# FM_VCO_Transmitter.net
KiCad netlist of a schematic drawn in EAGLE
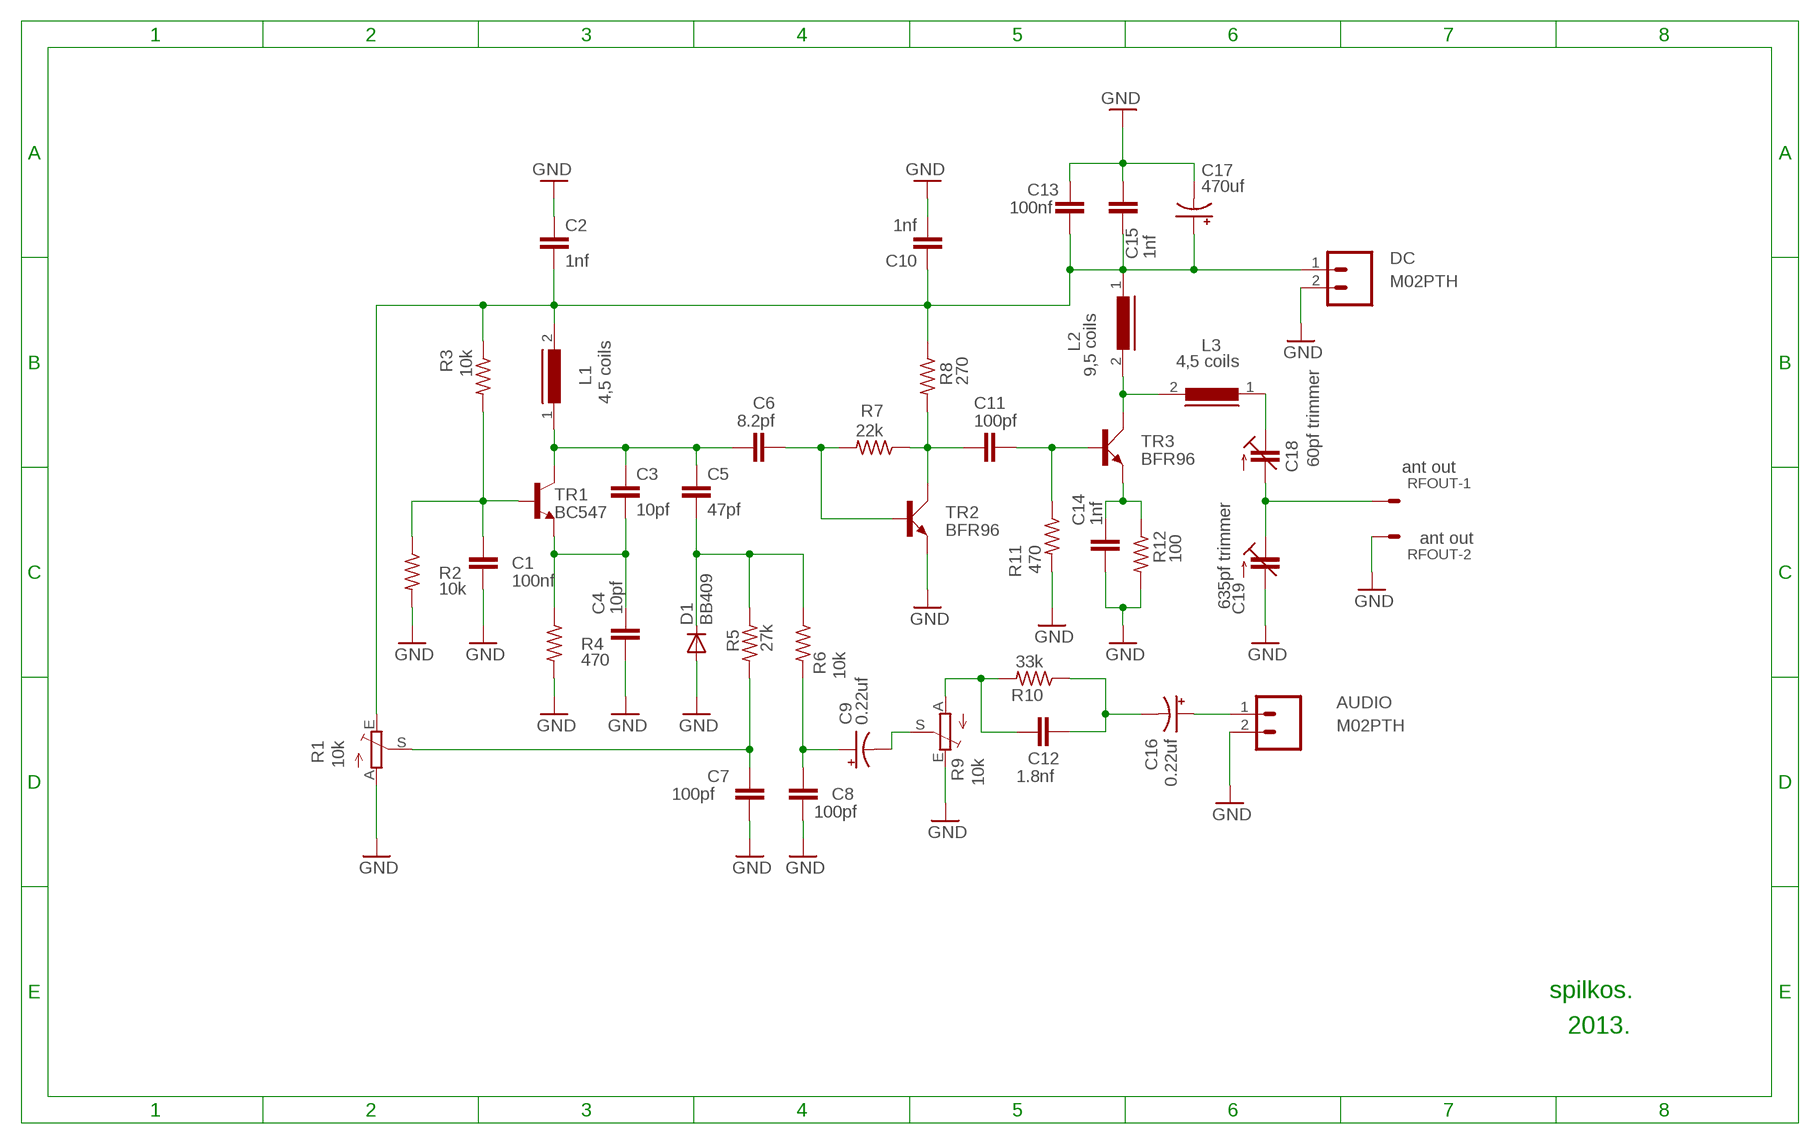
[diagram p0: schematic, sheet 1]

(export (version "E")
  (design (tool "Eeschema 10.0.6"))
  (components
    (comp (ref "AUDIO")
      (value "M02PTH")
      (footprint "eagle-import:1X02")
      (libsource (lib "eagle-import") (part "M02PTH"))
    )
    (comp (ref "C1")
      (value "100nf")
      (footprint "eagle-import:C025-024X044")
      (libsource (lib "eagle-import") (part "C-EU025-024X044"))
    )
    (comp (ref "C2")
      (value "1nf")
      (footprint "eagle-import:C025-024X044")
      (libsource (lib "eagle-import") (part "C-EU025-024X044"))
    )
    (comp (ref "C3")
      (value "10pf")
      (footprint "eagle-import:C025-024X044")
      (libsource (lib "eagle-import") (part "C-EU025-024X044"))
    )
    (comp (ref "C4")
      (value "10pf")
      (footprint "eagle-import:C025-024X044")
      (libsource (lib "eagle-import") (part "C-EU025-024X044"))
    )
    (comp (ref "C5")
      (value "47pf")
      (footprint "eagle-import:C025-024X044")
      (libsource (lib "eagle-import") (part "C-EU025-024X044"))
    )
    (comp (ref "C6")
      (value "8.2pf")
      (footprint "eagle-import:C025-024X044")
      (libsource (lib "eagle-import") (part "C-EU025-024X044"))
    )
    (comp (ref "C7")
      (value "100pf")
      (footprint "eagle-import:C025-024X044")
      (libsource (lib "eagle-import") (part "C-EU025-024X044"))
    )
    (comp (ref "C8")
      (value "100pf")
      (footprint "eagle-import:C025-024X044")
      (libsource (lib "eagle-import") (part "C-EU025-024X044"))
    )
    (comp (ref "C9")
      (value "0.22uf")
      (footprint "eagle-import:E2,5-6E")
      (libsource (lib "eagle-import") (part "CPOL-USE2,5-6E"))
    )
    (comp (ref "C10")
      (value "1nf")
      (footprint "eagle-import:C025-024X044")
      (libsource (lib "eagle-import") (part "C-EU025-024X044"))
    )
    (comp (ref "C11")
      (value "100pf")
      (footprint "eagle-import:C025-024X044")
      (libsource (lib "eagle-import") (part "C-EU025-024X044"))
    )
    (comp (ref "C12")
      (value "1.8nf")
      (footprint "eagle-import:C025-024X044")
      (libsource (lib "eagle-import") (part "C-EU025-024X044"))
    )
    (comp (ref "C13")
      (value "100nf")
      (footprint "eagle-import:C025-024X044")
      (libsource (lib "eagle-import") (part "C-EU025-024X044"))
    )
    (comp (ref "C14")
      (value "1nf")
      (footprint "eagle-import:C025-024X044")
      (libsource (lib "eagle-import") (part "C-EU025-024X044"))
    )
    (comp (ref "C15")
      (value "1nf")
      (footprint "eagle-import:C025-024X044")
      (libsource (lib "eagle-import") (part "C-EU025-024X044"))
    )
    (comp (ref "C16")
      (value "0.22uf")
      (footprint "eagle-import:E2,5-6E")
      (libsource (lib "eagle-import") (part "CPOL-USE2,5-6E"))
    )
    (comp (ref "C17")
      (value "470uf")
      (footprint "eagle-import:E2,5-6E")
      (libsource (lib "eagle-import") (part "CPOL-USE2,5-6E"))
    )
    (comp (ref "C18")
      (value "60pf trimmer")
      (footprint "eagle-import:CTRIMTZ03")
      (libsource (lib "eagle-import") (part "C-TRIMMTZ03"))
    )
    (comp (ref "C19")
      (value "635pf trimmer")
      (footprint "eagle-import:CTRIMTZ03")
      (libsource (lib "eagle-import") (part "C-TRIMMTZ03"))
    )
    (comp (ref "D1")
      (value "BB409")
      (footprint "eagle-import:DO35-10")
      (libsource (lib "eagle-import") (part "BA243A"))
    )
    (comp (ref "DC")
      (value "M02PTH")
      (footprint "eagle-import:1X02")
      (libsource (lib "eagle-import") (part "M02PTH"))
    )
    (comp (ref "L1")
      (value "4,5 coils")
      (footprint "eagle-import:82114R")
      (libsource (lib "eagle-import") (part "82114R"))
    )
    (comp (ref "L2")
      (value "9,5 coils")
      (footprint "eagle-import:82114R")
      (libsource (lib "eagle-import") (part "82114R"))
    )
    (comp (ref "L3")
      (value "4,5 coils")
      (footprint "eagle-import:82114R")
      (libsource (lib "eagle-import") (part "82114R"))
    )
    (comp (ref "R1")
      (value "10k")
      (footprint "eagle-import:B25P")
      (libsource (lib "eagle-import") (part "TRIM_EU-B25P"))
    )
    (comp (ref "R2")
      (value "10k")
      (footprint "eagle-import:0309V")
      (libsource (lib "eagle-import") (part "R-US_0309/V"))
    )
    (comp (ref "R3")
      (value "10k")
      (footprint "eagle-import:0309V")
      (libsource (lib "eagle-import") (part "R-US_0309/V"))
    )
    (comp (ref "R4")
      (value "470")
      (footprint "eagle-import:0309V")
      (libsource (lib "eagle-import") (part "R-US_0309/V"))
    )
    (comp (ref "R5")
      (value "27k")
      (footprint "eagle-import:0309V")
      (libsource (lib "eagle-import") (part "R-US_0309/V"))
    )
    (comp (ref "R6")
      (value "10k")
      (footprint "eagle-import:0309V")
      (libsource (lib "eagle-import") (part "R-US_0309/V"))
    )
    (comp (ref "R7")
      (value "22k")
      (footprint "eagle-import:0309V")
      (libsource (lib "eagle-import") (part "R-US_0309/V"))
    )
    (comp (ref "R8")
      (value "270")
      (footprint "eagle-import:0309V")
      (libsource (lib "eagle-import") (part "R-US_0309/V"))
    )
    (comp (ref "R9")
      (value "10k")
      (footprint "eagle-import:B25P")
      (libsource (lib "eagle-import") (part "TRIM_EU-B25P"))
    )
    (comp (ref "R10")
      (value "33k")
      (footprint "eagle-import:0309V")
      (libsource (lib "eagle-import") (part "R-US_0309/V"))
    )
    (comp (ref "R11")
      (value "470")
      (footprint "eagle-import:0309V")
      (libsource (lib "eagle-import") (part "R-US_0309/V"))
    )
    (comp (ref "R12")
      (value "100")
      (footprint "eagle-import:0309V")
      (libsource (lib "eagle-import") (part "R-US_0309/V"))
    )
    (comp (ref "RFOUT")
      (value "ant out")
      (footprint "eagle-import:332-02")
      (libsource (lib "eagle-import") (part "332-02"))
    )
    (comp (ref "TR1")
      (value "BC547")
      (footprint "eagle-import:TO92")
      (libsource (lib "eagle-import") (part "BC547"))
    )
    (comp (ref "TR2")
      (value "BFR96")
      (footprint "eagle-import:SOT37")
      (libsource (lib "eagle-import") (part "BFR96"))
    )
    (comp (ref "TR3")
      (value "BFR96")
      (footprint "eagle-import:SOT37")
      (libsource (lib "eagle-import") (part "BFR96"))
    )
  )
  (nets
    (net (code "1") (name "GND") (class "Default")
      (node (ref "AUDIO") (pin "2") (pinfunction "2_2") (pintype "passive"))
      (node (ref "C1") (pin "2") (pinfunction "2_2") (pintype "passive"))
      (node (ref "C10") (pin "2") (pinfunction "2_2") (pintype "passive"))
      (node (ref "C13") (pin "1") (pinfunction "1_1") (pintype "passive"))
      (node (ref "C14") (pin "2") (pinfunction "2_2") (pintype "passive"))
      (node (ref "C15") (pin "1") (pinfunction "1_1") (pintype "passive"))
      (node (ref "C17") (pin "-") (pinfunction "-_-") (pintype "passive"))
      (node (ref "C19") (pin "2") (pinfunction "A_2") (pintype "passive"))
      (node (ref "C2") (pin "1") (pinfunction "1_1") (pintype "passive"))
      (node (ref "C4") (pin "2") (pinfunction "2_2") (pintype "passive"))
      (node (ref "C7") (pin "2") (pinfunction "2_2") (pintype "passive"))
      (node (ref "C8") (pin "2") (pinfunction "2_2") (pintype "passive"))
      (node (ref "D1") (pin "A") (pinfunction "A_A") (pintype "passive"))
      (node (ref "DC") (pin "2") (pinfunction "2_2") (pintype "passive"))
      (node (ref "R1") (pin "A") (pinfunction "A_A") (pintype "passive"))
      (node (ref "R11") (pin "2") (pinfunction "2_2") (pintype "passive"))
      (node (ref "R12") (pin "2") (pinfunction "2_2") (pintype "passive"))
      (node (ref "R2") (pin "2") (pinfunction "2_2") (pintype "passive"))
      (node (ref "R4") (pin "2") (pinfunction "2_2") (pintype "passive"))
      (node (ref "R9") (pin "E") (pinfunction "E_E") (pintype "passive"))
      (node (ref "RFOUT") (pin "2") (pinfunction "S_2") (pintype "passive"))
      (node (ref "TR2") (pin "2") (pinfunction "E_2") (pintype "passive"))
    )
    (net (code "2") (name "Net-(AUDIO-Pad1)") (class "Default")
      (node (ref "AUDIO") (pin "1") (pinfunction "1_1") (pintype "passive"))
      (node (ref "C16") (pin "+") (pinfunction "+_+") (pintype "passive"))
    )
    (net (code "3") (name "Net-(C5-Pad2)") (class "Default")
      (node (ref "C5") (pin "2") (pinfunction "2_2") (pintype "passive"))
      (node (ref "D1") (pin "C") (pinfunction "C_C") (pintype "passive"))
      (node (ref "R5") (pin "1") (pinfunction "1_1") (pintype "passive"))
      (node (ref "R6") (pin "1") (pinfunction "1_1") (pintype "passive"))
    )
    (net (code "4") (name "Net-(C7-Pad1)") (class "Default")
      (node (ref "C7") (pin "1") (pinfunction "1_1") (pintype "passive"))
      (node (ref "R1") (pin "S") (pinfunction "S_S") (pintype "passive"))
      (node (ref "R5") (pin "2") (pinfunction "2_2") (pintype "passive"))
    )
    (net (code "5") (name "Net-(C8-Pad1)") (class "Default")
      (node (ref "C8") (pin "1") (pinfunction "1_1") (pintype "passive"))
      (node (ref "C9") (pin "+") (pinfunction "+_+") (pintype "passive"))
      (node (ref "R6") (pin "2") (pinfunction "2_2") (pintype "passive"))
    )
    (net (code "6") (name "Net-(C9-Pad-)") (class "Default")
      (node (ref "C9") (pin "-") (pinfunction "-_-") (pintype "passive"))
      (node (ref "R9") (pin "S") (pinfunction "S_S") (pintype "passive"))
    )
    (net (code "7") (name "Net-(C10-Pad1)") (class "Default")
      (node (ref "C10") (pin "1") (pinfunction "1_1") (pintype "passive"))
      (node (ref "C13") (pin "2") (pinfunction "2_2") (pintype "passive"))
      (node (ref "C15") (pin "2") (pinfunction "2_2") (pintype "passive"))
      (node (ref "C17") (pin "+") (pinfunction "+_+") (pintype "passive"))
      (node (ref "C2") (pin "2") (pinfunction "2_2") (pintype "passive"))
      (node (ref "DC") (pin "1") (pinfunction "1_1") (pintype "passive"))
      (node (ref "L1") (pin "2") (pinfunction "2_2") (pintype "passive"))
      (node (ref "L2") (pin "1") (pinfunction "1_1") (pintype "passive"))
      (node (ref "R1") (pin "E") (pinfunction "E_E") (pintype "passive"))
      (node (ref "R3") (pin "1") (pinfunction "1_1") (pintype "passive"))
      (node (ref "R8") (pin "1") (pinfunction "1_1") (pintype "passive"))
    )
    (net (code "8") (name "Net-(C12-Pad1)") (class "Default")
      (node (ref "C12") (pin "1") (pinfunction "1_1") (pintype "passive"))
      (node (ref "R10") (pin "2") (pinfunction "2_2") (pintype "passive"))
      (node (ref "R9") (pin "A") (pinfunction "A_A") (pintype "passive"))
    )
    (net (code "9") (name "Net-(C12-Pad2)") (class "Default")
      (node (ref "C12") (pin "2") (pinfunction "2_2") (pintype "passive"))
      (node (ref "C16") (pin "-") (pinfunction "-_-") (pintype "passive"))
      (node (ref "R10") (pin "1") (pinfunction "1_1") (pintype "passive"))
    )
    (net (code "10") (name "Net-(C18-A)") (class "Default")
      (node (ref "C18") (pin "2") (pinfunction "A_2") (pintype "passive"))
      (node (ref "C19") (pin "1") (pinfunction "E_1") (pintype "passive"))
      (node (ref "RFOUT") (pin "1") (pinfunction "S_1") (pintype "passive"))
    )
    (net (code "11") (name "Net-(C18-E)") (class "Default")
      (node (ref "C18") (pin "1") (pinfunction "E_1") (pintype "passive"))
      (node (ref "L3") (pin "1") (pinfunction "1_1") (pintype "passive"))
    )
    (net (code "12") (name "Net-(TR1-B)") (class "Default")
      (node (ref "C1") (pin "1") (pinfunction "1_1") (pintype "passive"))
      (node (ref "R2") (pin "1") (pinfunction "1_1") (pintype "passive"))
      (node (ref "R3") (pin "2") (pinfunction "2_2") (pintype "passive"))
      (node (ref "TR1") (pin "2") (pinfunction "B_2") (pintype "passive"))
    )
    (net (code "13") (name "Net-(TR1-C)") (class "Default")
      (node (ref "C3") (pin "1") (pinfunction "1_1") (pintype "passive"))
      (node (ref "C5") (pin "1") (pinfunction "1_1") (pintype "passive"))
      (node (ref "C6") (pin "1") (pinfunction "1_1") (pintype "passive"))
      (node (ref "L1") (pin "1") (pinfunction "1_1") (pintype "passive"))
      (node (ref "TR1") (pin "3") (pinfunction "C_3") (pintype "passive"))
    )
    (net (code "14") (name "Net-(TR1-E)") (class "Default")
      (node (ref "C3") (pin "2") (pinfunction "2_2") (pintype "passive"))
      (node (ref "C4") (pin "1") (pinfunction "1_1") (pintype "passive"))
      (node (ref "R4") (pin "1") (pinfunction "1_1") (pintype "passive"))
      (node (ref "TR1") (pin "1") (pinfunction "E_1") (pintype "passive"))
    )
    (net (code "15") (name "Net-(TR2-B)") (class "Default")
      (node (ref "C6") (pin "2") (pinfunction "2_2") (pintype "passive"))
      (node (ref "R7") (pin "2") (pinfunction "2_2") (pintype "passive"))
      (node (ref "TR2") (pin "3") (pinfunction "B_3") (pintype "passive"))
    )
    (net (code "16") (name "Net-(TR2-C)") (class "Default")
      (node (ref "C11") (pin "1") (pinfunction "1_1") (pintype "passive"))
      (node (ref "R7") (pin "1") (pinfunction "1_1") (pintype "passive"))
      (node (ref "R8") (pin "2") (pinfunction "2_2") (pintype "passive"))
      (node (ref "TR2") (pin "1") (pinfunction "C_1") (pintype "passive"))
    )
    (net (code "17") (name "Net-(TR3-B)") (class "Default")
      (node (ref "C11") (pin "2") (pinfunction "2_2") (pintype "passive"))
      (node (ref "R11") (pin "1") (pinfunction "1_1") (pintype "passive"))
      (node (ref "TR3") (pin "3") (pinfunction "B_3") (pintype "passive"))
    )
    (net (code "18") (name "Net-(TR3-C)") (class "Default")
      (node (ref "L2") (pin "2") (pinfunction "2_2") (pintype "passive"))
      (node (ref "L3") (pin "2") (pinfunction "2_2") (pintype "passive"))
      (node (ref "TR3") (pin "1") (pinfunction "C_1") (pintype "passive"))
    )
    (net (code "19") (name "Net-(TR3-E)") (class "Default")
      (node (ref "C14") (pin "1") (pinfunction "1_1") (pintype "passive"))
      (node (ref "R12") (pin "1") (pinfunction "1_1") (pintype "passive"))
      (node (ref "TR3") (pin "2") (pinfunction "E_2") (pintype "passive"))
    )
  )
)
